# P2H-001.net
KiCad netlist of a schematic drawn in EAGLE
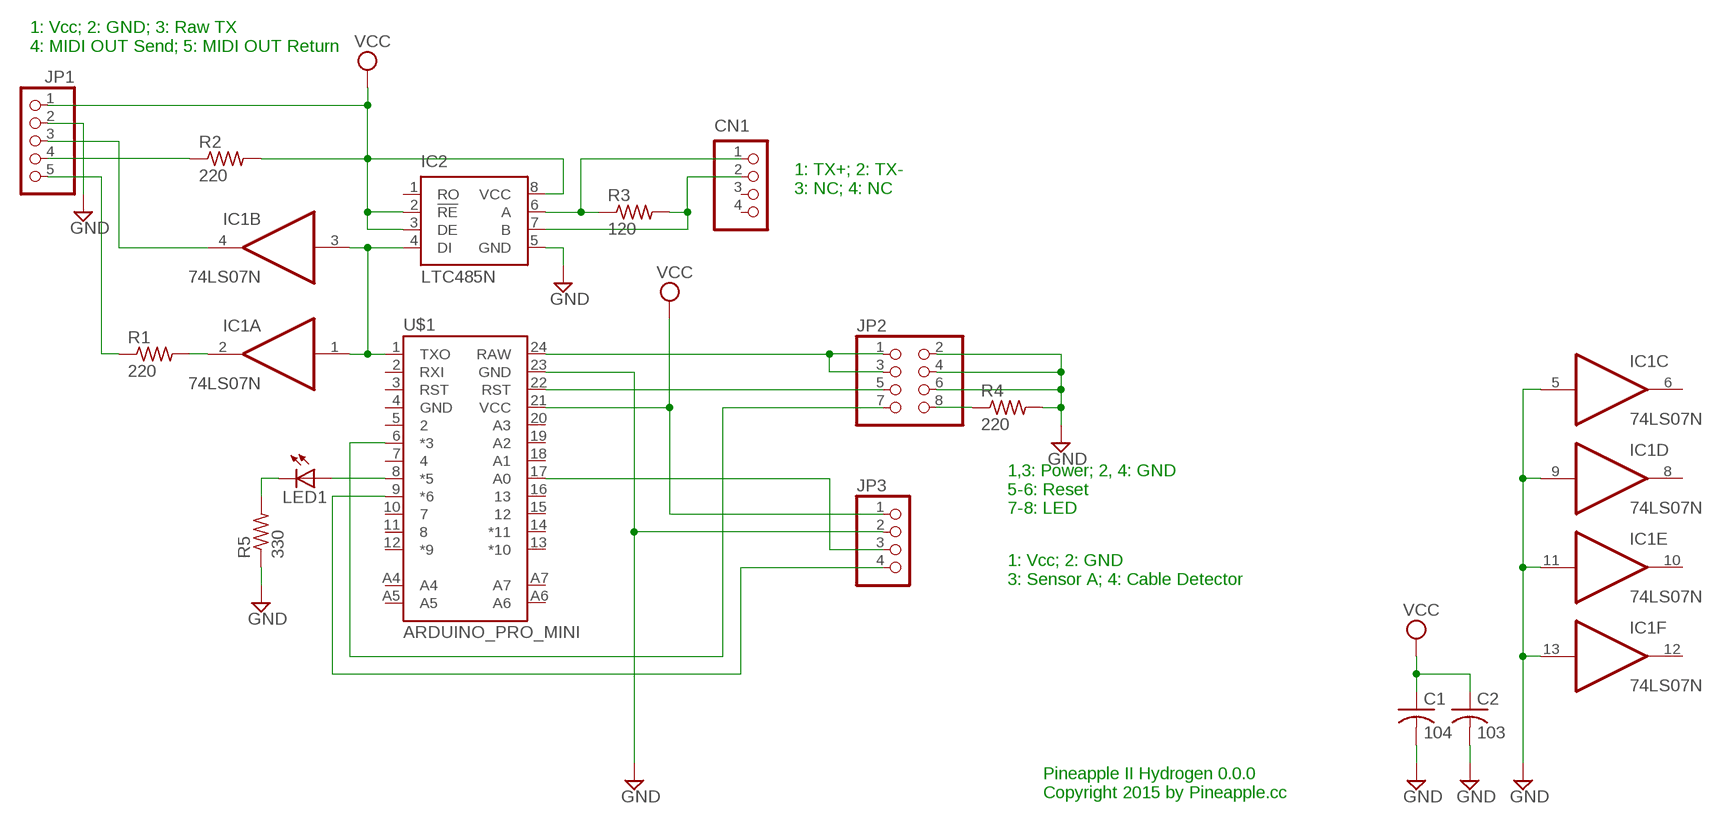
[diagram p0: schematic, sheet 1]

(export (version "E")
  (design (tool "Eeschema 10.0.6"))
  (components
    (comp (ref "C1")
      (value "104")
      (footprint "eagle-import:C025-025X050")
      (libsource (lib "eagle-import") (part "C-US025-025X050"))
    )
    (comp (ref "C2")
      (value "103")
      (footprint "eagle-import:C025-025X050")
      (libsource (lib "eagle-import") (part "C-US025-025X050"))
    )
    (comp (ref "CN1")
      (value "B4B-PH-K-S")
      (footprint "eagle-import:B4B-PH-K-S")
      (libsource (lib "eagle-import") (part "B4B-PH-K-S"))
    )
    (comp (ref "IC1")
      (value "74LS07N")
      (footprint "eagle-import:DIL14")
      (libsource (lib "eagle-import") (part "7407NLS"))
    )
    (comp (ref "IC2")
      (value "LTC485N")
      (footprint "eagle-import:DIL08")
      (libsource (lib "eagle-import") (part "LTC485N"))
    )
    (comp (ref "JP1")
      (value "PINHD-1X5")
      (footprint "eagle-import:1X05")
      (libsource (lib "eagle-import") (part "PINHD-1X5"))
    )
    (comp (ref "JP2")
      (value "PINHD-2X4")
      (footprint "eagle-import:2X04")
      (libsource (lib "eagle-import") (part "PINHD-2X4"))
    )
    (comp (ref "JP3")
      (value "PINHD-1X4")
      (footprint "eagle-import:1X04")
      (libsource (lib "eagle-import") (part "PINHD-1X4"))
    )
    (comp (ref "LED1")
      (value "LED3MM")
      (footprint "eagle-import:LED3MM")
      (libsource (lib "eagle-import") (part "LED3MM"))
    )
    (comp (ref "R1")
      (value "220")
      (footprint "eagle-import:0204_5")
      (libsource (lib "eagle-import") (part "R-US_0204/5"))
    )
    (comp (ref "R2")
      (value "220")
      (footprint "eagle-import:0204_5")
      (libsource (lib "eagle-import") (part "R-US_0204/5"))
    )
    (comp (ref "R3")
      (value "120")
      (footprint "eagle-import:0204_5")
      (libsource (lib "eagle-import") (part "R-US_0204/5"))
    )
    (comp (ref "R4")
      (value "220")
      (footprint "eagle-import:0204_5")
      (libsource (lib "eagle-import") (part "R-US_0204/5"))
    )
    (comp (ref "R5")
      (value "330")
      (footprint "eagle-import:0204_5")
      (libsource (lib "eagle-import") (part "R-US_0204/5"))
    )
    (comp (ref "U$1")
      (value "ARDUINO_PRO_MINI")
      (footprint "eagle-import:ARDUINO_PRO_MINI")
      (libsource (lib "eagle-import") (part "ARDUINO_PRO_MINI"))
    )
  )
  (nets
    (net (code "1") (name "GND") (class "Default")
      (node (ref "C1") (pin "2") (pinfunction "2_2") (pintype "passive"))
      (node (ref "C2") (pin "2") (pinfunction "2_2") (pintype "passive"))
      (node (ref "IC1") (pin "11") (pinfunction "I_11") (pintype "input"))
      (node (ref "IC1") (pin "13") (pinfunction "I_13") (pintype "input"))
      (node (ref "IC1") (pin "5") (pinfunction "I_5") (pintype "input"))
      (node (ref "IC1") (pin "9") (pinfunction "I_9") (pintype "input"))
      (node (ref "IC2") (pin "5") (pinfunction "GND_5") (pintype "input"))
      (node (ref "JP1") (pin "2") (pinfunction "2_2") (pintype "passive"))
      (node (ref "JP2") (pin "2") (pinfunction "2_2") (pintype "passive"))
      (node (ref "JP2") (pin "4") (pinfunction "4_4") (pintype "passive"))
      (node (ref "JP2") (pin "6") (pinfunction "6_6") (pintype "passive"))
      (node (ref "JP3") (pin "2") (pinfunction "2_2") (pintype "passive"))
      (node (ref "R4") (pin "2") (pinfunction "2_2") (pintype "passive"))
      (node (ref "R5") (pin "1") (pinfunction "1_1") (pintype "passive"))
      (node (ref "U$1") (pin "23") (pinfunction "GND_23") (pintype "bidirectional"))
    )
    (net (code "2") (name "Net-(IC1A-I)") (class "Default")
      (node (ref "IC1") (pin "1") (pinfunction "I_1") (pintype "input"))
      (node (ref "IC1") (pin "3") (pinfunction "I_3") (pintype "input"))
      (node (ref "IC2") (pin "4") (pinfunction "DI_4") (pintype "input"))
      (node (ref "U$1") (pin "1") (pinfunction "TXO_1") (pintype "bidirectional"))
    )
    (net (code "3") (name "Net-(IC1A-O)") (class "Default")
      (node (ref "IC1") (pin "2") (pinfunction "O_2") (pintype "open_collector"))
      (node (ref "R1") (pin "2") (pinfunction "2_2") (pintype "passive"))
    )
    (net (code "4") (name "Net-(IC1B-O)") (class "Default")
      (node (ref "IC1") (pin "4") (pinfunction "O_4") (pintype "open_collector"))
      (node (ref "JP1") (pin "3") (pinfunction "3_3") (pintype "passive"))
    )
    (net (code "5") (name "Net-(IC2-A)") (class "Default")
      (node (ref "CN1") (pin "1") (pinfunction "1_1") (pintype "passive"))
      (node (ref "IC2") (pin "6") (pinfunction "A_6") (pintype "bidirectional"))
      (node (ref "R3") (pin "1") (pinfunction "1_1") (pintype "passive"))
    )
    (net (code "6") (name "Net-(IC2-B)") (class "Default")
      (node (ref "CN1") (pin "2") (pinfunction "2_2") (pintype "passive"))
      (node (ref "IC2") (pin "7") (pinfunction "B_7") (pintype "bidirectional"))
      (node (ref "R3") (pin "2") (pinfunction "2_2") (pintype "passive"))
    )
    (net (code "7") (name "Net-(JP1-Pad4)") (class "Default")
      (node (ref "JP1") (pin "4") (pinfunction "4_4") (pintype "passive"))
      (node (ref "R2") (pin "1") (pinfunction "1_1") (pintype "passive"))
    )
    (net (code "8") (name "Net-(JP1-Pad5)") (class "Default")
      (node (ref "JP1") (pin "5") (pinfunction "5_5") (pintype "passive"))
      (node (ref "R1") (pin "1") (pinfunction "1_1") (pintype "passive"))
    )
    (net (code "9") (name "Net-(JP2-Pad5)") (class "Default")
      (node (ref "JP2") (pin "5") (pinfunction "5_5") (pintype "passive"))
      (node (ref "U$1") (pin "22") (pinfunction "RST_22") (pintype "bidirectional"))
    )
    (net (code "10") (name "Net-(JP2-Pad8)") (class "Default")
      (node (ref "JP2") (pin "8") (pinfunction "8_8") (pintype "passive"))
      (node (ref "R4") (pin "1") (pinfunction "1_1") (pintype "passive"))
    )
    (net (code "11") (name "Net-(LED1-C)") (class "Default")
      (node (ref "LED1") (pin "K") (pinfunction "C_K") (pintype "passive"))
      (node (ref "R5") (pin "2") (pinfunction "2_2") (pintype "passive"))
    )
    (net (code "12") (name "Net-(U$1-*3)") (class "Default")
      (node (ref "JP2") (pin "7") (pinfunction "7_7") (pintype "passive"))
      (node (ref "U$1") (pin "6") (pinfunction "*3_6") (pintype "bidirectional"))
    )
    (net (code "13") (name "Net-(U$1-*5)") (class "Default")
      (node (ref "LED1") (pin "A") (pinfunction "A_A") (pintype "passive"))
      (node (ref "U$1") (pin "8") (pinfunction "*5_8") (pintype "bidirectional"))
    )
    (net (code "14") (name "Net-(U$1-*6)") (class "Default")
      (node (ref "JP3") (pin "4") (pinfunction "4_4") (pintype "passive"))
      (node (ref "U$1") (pin "9") (pinfunction "*6_9") (pintype "bidirectional"))
    )
    (net (code "15") (name "Net-(U$1-A0)") (class "Default")
      (node (ref "JP3") (pin "3") (pinfunction "3_3") (pintype "passive"))
      (node (ref "U$1") (pin "17") (pinfunction "A0_17") (pintype "bidirectional"))
    )
    (net (code "16") (name "Net-(U$1-RAW)") (class "Default")
      (node (ref "JP2") (pin "1") (pinfunction "1_1") (pintype "passive"))
      (node (ref "JP2") (pin "3") (pinfunction "3_3") (pintype "passive"))
      (node (ref "U$1") (pin "24") (pinfunction "RAW_24") (pintype "bidirectional"))
    )
    (net (code "17") (name "VCC") (class "Default")
      (node (ref "C1") (pin "1") (pinfunction "1_1") (pintype "passive"))
      (node (ref "C2") (pin "1") (pinfunction "1_1") (pintype "passive"))
      (node (ref "IC2") (pin "2") (pinfunction "~{RE}_2") (pintype "input"))
      (node (ref "IC2") (pin "3") (pinfunction "DE_3") (pintype "input"))
      (node (ref "IC2") (pin "8") (pinfunction "VCC_8") (pintype "input"))
      (node (ref "JP1") (pin "1") (pinfunction "1_1") (pintype "passive"))
      (node (ref "JP3") (pin "1") (pinfunction "1_1") (pintype "passive"))
      (node (ref "R2") (pin "2") (pinfunction "2_2") (pintype "passive"))
      (node (ref "U$1") (pin "21") (pinfunction "VCC_21") (pintype "bidirectional"))
    )
    (net (code "18") (name "unconnected-(CN1-Pad3)") (class "Default")
      (node (ref "CN1") (pin "3") (pinfunction "3_3") (pintype "passive"))
    )
    (net (code "19") (name "unconnected-(CN1-Pad4)") (class "Default")
      (node (ref "CN1") (pin "4") (pinfunction "4_4") (pintype "passive"))
    )
    (net (code "20") (name "unconnected-(IC1C-O-Pad6)") (class "Default")
      (node (ref "IC1") (pin "6") (pinfunction "O_6") (pintype "open_collector"))
    )
    (net (code "21") (name "unconnected-(IC1D-O-Pad8)") (class "Default")
      (node (ref "IC1") (pin "8") (pinfunction "O_8") (pintype "open_collector"))
    )
    (net (code "22") (name "unconnected-(IC1E-O-Pad10)") (class "Default")
      (node (ref "IC1") (pin "10") (pinfunction "O_10") (pintype "open_collector"))
    )
    (net (code "23") (name "unconnected-(IC1F-O-Pad12)") (class "Default")
      (node (ref "IC1") (pin "12") (pinfunction "O_12") (pintype "open_collector"))
    )
    (net (code "24") (name "unconnected-(IC2-RO-Pad1)") (class "Default")
      (node (ref "IC2") (pin "1") (pinfunction "RO_1") (pintype "output"))
    )
    (net (code "25") (name "unconnected-(U$1-*9-Pad12)") (class "Default")
      (node (ref "U$1") (pin "12") (pinfunction "*9_12") (pintype "bidirectional"))
    )
    (net (code "26") (name "unconnected-(U$1-*10-Pad13)") (class "Default")
      (node (ref "U$1") (pin "13") (pinfunction "*10_13") (pintype "bidirectional"))
    )
    (net (code "27") (name "unconnected-(U$1-*11-Pad14)") (class "Default")
      (node (ref "U$1") (pin "14") (pinfunction "*11_14") (pintype "bidirectional"))
    )
    (net (code "28") (name "unconnected-(U$1-2-Pad5)") (class "Default")
      (node (ref "U$1") (pin "5") (pinfunction "2_5") (pintype "bidirectional"))
    )
    (net (code "29") (name "unconnected-(U$1-4-Pad7)") (class "Default")
      (node (ref "U$1") (pin "7") (pinfunction "4_7") (pintype "bidirectional"))
    )
    (net (code "30") (name "unconnected-(U$1-7-Pad10)") (class "Default")
      (node (ref "U$1") (pin "10") (pinfunction "7_10") (pintype "bidirectional"))
    )
    (net (code "31") (name "unconnected-(U$1-8-Pad11)") (class "Default")
      (node (ref "U$1") (pin "11") (pinfunction "8_11") (pintype "bidirectional"))
    )
    (net (code "32") (name "unconnected-(U$1-12-Pad15)") (class "Default")
      (node (ref "U$1") (pin "15") (pinfunction "12_15") (pintype "bidirectional"))
    )
    (net (code "33") (name "unconnected-(U$1-13-Pad16)") (class "Default")
      (node (ref "U$1") (pin "16") (pinfunction "13_16") (pintype "bidirectional"))
    )
    (net (code "34") (name "unconnected-(U$1-A1-Pad18)") (class "Default")
      (node (ref "U$1") (pin "18") (pinfunction "A1_18") (pintype "bidirectional"))
    )
    (net (code "35") (name "unconnected-(U$1-A2-Pad19)") (class "Default")
      (node (ref "U$1") (pin "19") (pinfunction "A2_19") (pintype "bidirectional"))
    )
    (net (code "36") (name "unconnected-(U$1-A3-Pad20)") (class "Default")
      (node (ref "U$1") (pin "20") (pinfunction "A3_20") (pintype "bidirectional"))
    )
    (net (code "37") (name "unconnected-(U$1-GND-Pad4)") (class "Default")
      (node (ref "U$1") (pin "4") (pinfunction "GND_4") (pintype "bidirectional"))
    )
    (net (code "38") (name "unconnected-(U$1-PadA4)") (class "Default")
      (node (ref "U$1") (pin "A4") (pinfunction "A4_A4") (pintype "bidirectional"))
    )
    (net (code "39") (name "unconnected-(U$1-PadA5)") (class "Default")
      (node (ref "U$1") (pin "A5") (pinfunction "A5_A5") (pintype "bidirectional"))
    )
    (net (code "40") (name "unconnected-(U$1-PadA6)") (class "Default")
      (node (ref "U$1") (pin "A6") (pinfunction "A6_A6") (pintype "bidirectional"))
    )
    (net (code "41") (name "unconnected-(U$1-PadA7)") (class "Default")
      (node (ref "U$1") (pin "A7") (pinfunction "A7_A7") (pintype "bidirectional"))
    )
    (net (code "42") (name "unconnected-(U$1-RST-Pad3)") (class "Default")
      (node (ref "U$1") (pin "3") (pinfunction "RST_3") (pintype "bidirectional"))
    )
    (net (code "43") (name "unconnected-(U$1-RXI-Pad2)") (class "Default")
      (node (ref "U$1") (pin "2") (pinfunction "RXI_2") (pintype "bidirectional"))
    )
  )
)
